# remote-displayV2.net
KiCad netlist of a schematic drawn in EAGLE
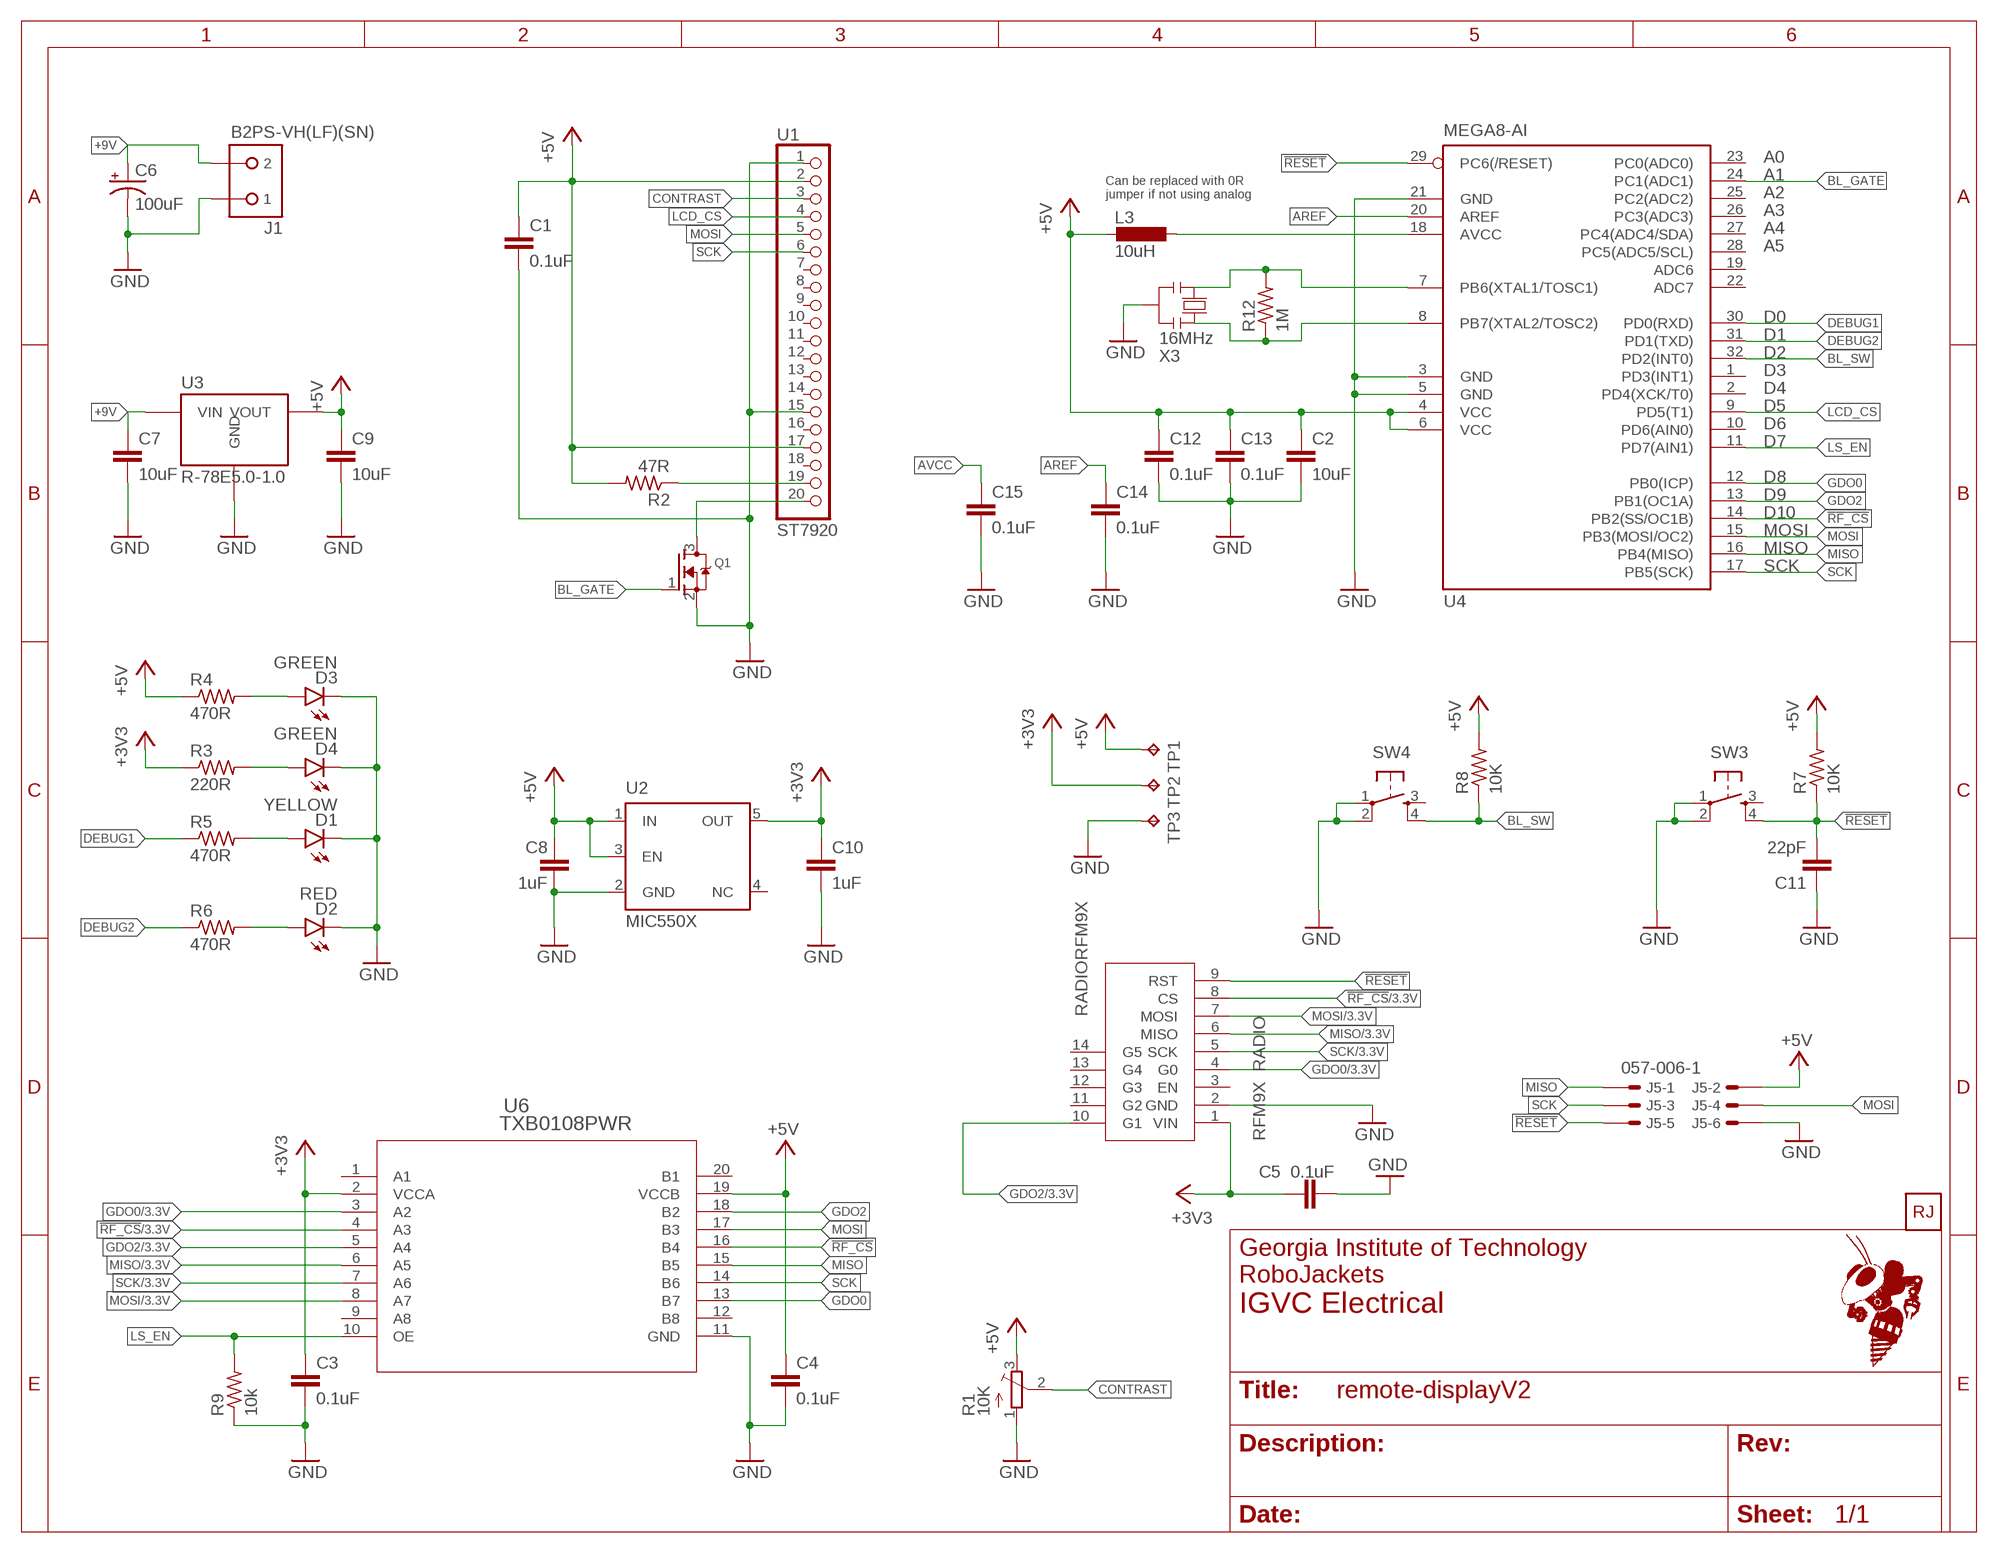
[diagram p0: schematic, sheet 1]

(export (version "E")
  (design (tool "Eeschema 10.0.6"))
  (components
    (comp (ref "C1")
      (value "0.1uF")
      (footprint "eagle-import:C0603")
      (libsource (lib "eagle-import") (part "resistor_348_C-EUC0603"))
    )
    (comp (ref "C2")
      (value "10uF")
      (footprint "eagle-import:C0805")
      (libsource (lib "eagle-import") (part "resistor_348_C-EUC0805"))
    )
    (comp (ref "C3")
      (value "0.1uF")
      (footprint "eagle-import:C0603")
      (libsource (lib "eagle-import") (part "C-EUC0603"))
    )
    (comp (ref "C4")
      (value "0.1uF")
      (footprint "eagle-import:C0603")
      (libsource (lib "eagle-import") (part "C-EUC0603"))
    )
    (comp (ref "C5")
      (value "0.1uF")
      (footprint "eagle-import:C0603")
      (libsource (lib "eagle-import") (part "resistor_348_C-EUC0603"))
    )
    (comp (ref "C6")
      (value "100uF")
      (footprint "eagle-import:E5-10,5")
      (libsource (lib "eagle-import") (part "CPOL-USE5-10.5"))
    )
    (comp (ref "C7")
      (value "10uF")
      (footprint "eagle-import:C0603")
      (libsource (lib "eagle-import") (part "C-EUC0603"))
    )
    (comp (ref "C8")
      (value "1uF")
      (footprint "eagle-import:C0603")
      (libsource (lib "eagle-import") (part "C-EUC0603"))
    )
    (comp (ref "C9")
      (value "10uF")
      (footprint "eagle-import:C0603")
      (libsource (lib "eagle-import") (part "C-EUC0603"))
    )
    (comp (ref "C10")
      (value "1uF")
      (footprint "eagle-import:C0603")
      (libsource (lib "eagle-import") (part "C-EUC0603"))
    )
    (comp (ref "C11")
      (value "22pF")
      (footprint "eagle-import:C0603")
      (libsource (lib "eagle-import") (part "resistor_348_C-EUC0603"))
    )
    (comp (ref "C12")
      (value "0.1uF")
      (footprint "eagle-import:C0603")
      (libsource (lib "eagle-import") (part "resistor_348_C-EUC0603"))
    )
    (comp (ref "C13")
      (value "0.1uF")
      (footprint "eagle-import:C0603")
      (libsource (lib "eagle-import") (part "resistor_348_C-EUC0603"))
    )
    (comp (ref "C14")
      (value "0.1uF")
      (footprint "eagle-import:C0603")
      (libsource (lib "eagle-import") (part "resistor_348_C-EUC0603"))
    )
    (comp (ref "C15")
      (value "0.1uF")
      (footprint "eagle-import:C0603")
      (libsource (lib "eagle-import") (part "resistor_348_C-EUC0603"))
    )
    (comp (ref "D1")
      (value "YELLOW")
      (footprint "eagle-import:LED3MM")
      (libsource (lib "eagle-import") (part "LED3MM"))
    )
    (comp (ref "D2")
      (value "RED")
      (footprint "eagle-import:LED3MM")
      (libsource (lib "eagle-import") (part "LED3MM"))
    )
    (comp (ref "D3")
      (value "GREEN")
      (footprint "eagle-import:LED3MM")
      (libsource (lib "eagle-import") (part "LED3MM"))
    )
    (comp (ref "D4")
      (value "GREEN")
      (footprint "eagle-import:LED3MM")
      (libsource (lib "eagle-import") (part "LED3MM"))
    )
    (comp (ref "J1")
      (value "B2PS-VH(LF)(SN)")
      (footprint "eagle-import:B2PS-CENTERED")
      (libsource (lib "eagle-import") (part "B2P?-VH(LF)(SN)S"))
    )
    (comp (ref "J5")
      (value "057-006-1")
      (footprint "eagle-import:057-006-1")
      (fields (field (name "DIGIKEY") "3M15451-ND"))
      (libsource (lib "eagle-import") (part "057-006-1"))
    )
    (comp (ref "L3")
      (value "10uH")
      (footprint "eagle-import:0805")
      (libsource (lib "eagle-import") (part "L-0805"))
    )
    (comp (ref "Q1")
      (value "MOSFET-NREFLOW")
      (footprint "eagle-import:SOT23")
      (libsource (lib "eagle-import") (part "MOSFET-NREFLOW"))
    )
    (comp (ref "R1")
      (value "10K")
      (footprint "eagle-import:TRIM-3386")
      (libsource (lib "eagle-import") (part "TRIMPOT3386"))
    )
    (comp (ref "R2")
      (value "47R")
      (footprint "eagle-import:R0805")
      (libsource (lib "eagle-import") (part "resistor_348_R-US_R0805"))
    )
    (comp (ref "R3")
      (value "220R")
      (footprint "eagle-import:R0603")
      (libsource (lib "eagle-import") (part "resistor_348_R-US_R0603"))
    )
    (comp (ref "R4")
      (value "470R")
      (footprint "eagle-import:R0603")
      (libsource (lib "eagle-import") (part "resistor_348_R-US_R0603"))
    )
    (comp (ref "R5")
      (value "470R")
      (footprint "eagle-import:R0603")
      (libsource (lib "eagle-import") (part "resistor_348_R-US_R0603"))
    )
    (comp (ref "R6")
      (value "470R")
      (footprint "eagle-import:R0603")
      (libsource (lib "eagle-import") (part "resistor_348_R-US_R0603"))
    )
    (comp (ref "R7")
      (value "10K")
      (footprint "eagle-import:R0603")
      (libsource (lib "eagle-import") (part "resistor_348_R-US_R0603"))
    )
    (comp (ref "R8")
      (value "10K")
      (footprint "eagle-import:R0603")
      (libsource (lib "eagle-import") (part "resistor_348_R-US_R0603"))
    )
    (comp (ref "R9")
      (value "10k")
      (footprint "eagle-import:R0603")
      (libsource (lib "eagle-import") (part "R-US_R0603"))
    )
    (comp (ref "R12")
      (value "1M")
      (footprint "eagle-import:R0603")
      (libsource (lib "eagle-import") (part "resistor_348_R-US_R0603"))
    )
    (comp (ref "SW3")
      (value "TL1105_A-H")
      (footprint "eagle-import:TL1105_A-H")
      (libsource (lib "eagle-import") (part "TL1105_A-H"))
    )
    (comp (ref "SW4")
      (value "TL1105_A-H")
      (footprint "eagle-import:TL1105_A-H")
      (libsource (lib "eagle-import") (part "TL1105_A-H"))
    )
    (comp (ref "TP1")
      (value "TPPAD1-17")
      (footprint "eagle-import:P1-17")
      (libsource (lib "eagle-import") (part "TPPAD1-17"))
    )
    (comp (ref "TP2")
      (value "TPPAD1-17")
      (footprint "eagle-import:P1-17")
      (libsource (lib "eagle-import") (part "TPPAD1-17"))
    )
    (comp (ref "TP3")
      (value "TPPAD1-17")
      (footprint "eagle-import:P1-17")
      (libsource (lib "eagle-import") (part "TPPAD1-17"))
    )
    (comp (ref "U$1")
      (value "RADIORFM9X")
      (footprint "eagle-import:RFM9X")
      (libsource (lib "eagle-import") (part "RADIORFM9X"))
    )
    (comp (ref "U$2")
      (value "ROBOBUZZ1.0X")
      (footprint "eagle-import:ROBOBUZZ_1.0X")
      (libsource (lib "eagle-import") (part "ROBOBUZZ1.0X"))
    )
    (comp (ref "U1")
      (value "ST7920")
      (footprint "eagle-import:ST7920-LCD")
      (libsource (lib "eagle-import") (part "ST7920"))
    )
    (comp (ref "U2")
      (value "MIC550X")
      (footprint "eagle-import:SOT23-DBV")
      (libsource (lib "eagle-import") (part "MIC550X"))
    )
    (comp (ref "U3")
      (value "R-78E5.0-1.0")
      (footprint "eagle-import:R-78E")
      (libsource (lib "eagle-import") (part "R-78E5.0-1.0"))
    )
    (comp (ref "U4")
      (value "MEGA8-AI")
      (footprint "eagle-import:TQFP32-08")
      (fields (field (name "MPN") "ATMEGA8-16AU"))
      (libsource (lib "eagle-import") (part "MEGA8-AI"))
    )
    (comp (ref "U6")
      (value "TXB0108PWR")
      (footprint "eagle-import:PW20")
      (libsource (lib "eagle-import") (part "TXB0108PWR"))
    )
    (comp (ref "X3")
      (value "16MHz")
      (footprint "eagle-import:RESONATOR")
      (fields (field (name "PART_NUMBER") "CSTCE16M0V53-R0"))
      (libsource (lib "eagle-import") (part "OSC_CSTCE16M0V53-R0"))
    )
  )
  (nets
    (net (code "1") (name "+3V3") (class "Default")
      (node (ref "C10") (pin "1") (pinfunction "1_1") (pintype "passive"))
      (node (ref "C3") (pin "1") (pinfunction "1_1") (pintype "passive"))
      (node (ref "C5") (pin "1") (pinfunction "1_1") (pintype "passive"))
      (node (ref "R3") (pin "1") (pinfunction "1_1") (pintype "passive"))
      (node (ref "TP2") (pin "TP") (pinfunction "TP_TP") (pintype "input"))
      (node (ref "U$1") (pin "1") (pinfunction "VIN_1") (pintype "bidirectional"))
      (node (ref "U2") (pin "5") (pinfunction "OUT_5") (pintype "passive"))
      (node (ref "U6") (pin "2") (pinfunction "VCCA_2") (pintype "power_in"))
    )
    (net (code "2") (name "+5V") (class "Default")
      (node (ref "C1") (pin "1") (pinfunction "1_1") (pintype "passive"))
      (node (ref "C12") (pin "1") (pinfunction "1_1") (pintype "passive"))
      (node (ref "C13") (pin "1") (pinfunction "1_1") (pintype "passive"))
      (node (ref "C2") (pin "1") (pinfunction "1_1") (pintype "passive"))
      (node (ref "C4") (pin "1") (pinfunction "1_1") (pintype "passive"))
      (node (ref "C8") (pin "1") (pinfunction "1_1") (pintype "passive"))
      (node (ref "C9") (pin "1") (pinfunction "1_1") (pintype "passive"))
      (node (ref "J5") (pin "2") (pinfunction "S_2") (pintype "passive"))
      (node (ref "L3") (pin "2") (pinfunction "2_2") (pintype "passive"))
      (node (ref "R1") (pin "3") (pinfunction "E_3") (pintype "passive"))
      (node (ref "R2") (pin "2") (pinfunction "2_2") (pintype "passive"))
      (node (ref "R4") (pin "1") (pinfunction "1_1") (pintype "passive"))
      (node (ref "R7") (pin "2") (pinfunction "2_2") (pintype "passive"))
      (node (ref "R8") (pin "2") (pinfunction "2_2") (pintype "passive"))
      (node (ref "TP1") (pin "TP") (pinfunction "TP_TP") (pintype "input"))
      (node (ref "U1") (pin "17") (pinfunction "17_17") (pintype "passive"))
      (node (ref "U1") (pin "2") (pinfunction "2_2") (pintype "passive"))
      (node (ref "U2") (pin "1") (pinfunction "IN_1") (pintype "input"))
      (node (ref "U2") (pin "3") (pinfunction "EN_3") (pintype "input"))
      (node (ref "U3") (pin "3") (pinfunction "VOUT_3") (pintype "bidirectional"))
      (node (ref "U4") (pin "4") (pinfunction "VCC_4") (pintype "power_in"))
      (node (ref "U4") (pin "6") (pinfunction "VCC_6") (pintype "power_in"))
      (node (ref "U6") (pin "19") (pinfunction "VCCB_19") (pintype "power_in"))
    )
    (net (code "3") (name "+9V") (class "Default")
      (node (ref "C6") (pin "+") (pinfunction "+_+") (pintype "passive"))
      (node (ref "C7") (pin "1") (pinfunction "1_1") (pintype "passive"))
      (node (ref "J1") (pin "2") (pinfunction "2_2") (pintype "bidirectional"))
      (node (ref "U3") (pin "1") (pinfunction "VIN_1") (pintype "bidirectional"))
    )
    (net (code "4") (name "/~{RESET}") (class "Default")
      (node (ref "C11") (pin "2") (pinfunction "2_2") (pintype "passive"))
      (node (ref "J5") (pin "5") (pinfunction "S_5") (pintype "passive"))
      (node (ref "R7") (pin "1") (pinfunction "1_1") (pintype "passive"))
      (node (ref "SW3") (pin "4") (pinfunction "4_4") (pintype "passive"))
      (node (ref "U$1") (pin "9") (pinfunction "RST_9") (pintype "bidirectional"))
      (node (ref "U4") (pin "29") (pinfunction "PC6(/RESET)_29") (pintype "bidirectional"))
    )
    (net (code "5") (name "/~{RF_CS}") (class "Default")
      (node (ref "U4") (pin "14") (pinfunction "PB2(SS/OC1B)_14") (pintype "bidirectional"))
      (node (ref "U6") (pin "16") (pinfunction "B4_16") (pintype "bidirectional"))
    )
    (net (code "6") (name "/~{RF_CS}{slash}3.3V") (class "Default")
      (node (ref "U$1") (pin "8") (pinfunction "CS_8") (pintype "bidirectional"))
      (node (ref "U6") (pin "4") (pinfunction "A3_4") (pintype "bidirectional"))
    )
    (net (code "7") (name "AREF") (class "Default")
      (node (ref "C14") (pin "1") (pinfunction "1_1") (pintype "passive"))
      (node (ref "U4") (pin "20") (pinfunction "AREF_20") (pintype "passive"))
    )
    (net (code "8") (name "AVCC") (class "Default")
      (node (ref "C15") (pin "1") (pinfunction "1_1") (pintype "passive"))
      (node (ref "L3") (pin "1") (pinfunction "1_1") (pintype "passive"))
      (node (ref "U4") (pin "18") (pinfunction "AVCC_18") (pintype "power_in"))
    )
    (net (code "9") (name "BL_GATE") (class "Default")
      (node (ref "Q1") (pin "1") (pinfunction "G_1") (pintype "bidirectional"))
      (node (ref "U4") (pin "24") (pinfunction "PC1(ADC1)_24") (pintype "bidirectional"))
    )
    (net (code "10") (name "BL_SW") (class "Default")
      (node (ref "R8") (pin "1") (pinfunction "1_1") (pintype "passive"))
      (node (ref "SW4") (pin "4") (pinfunction "4_4") (pintype "passive"))
      (node (ref "U4") (pin "32") (pinfunction "PD2(INT0)_32") (pintype "bidirectional"))
    )
    (net (code "11") (name "CONTRAST") (class "Default")
      (node (ref "R1") (pin "2") (pinfunction "S_2") (pintype "passive"))
      (node (ref "U1") (pin "3") (pinfunction "3_3") (pintype "passive"))
    )
    (net (code "12") (name "DEBUG1") (class "Default")
      (node (ref "R5") (pin "1") (pinfunction "1_1") (pintype "passive"))
      (node (ref "U4") (pin "30") (pinfunction "PD0(RXD)_30") (pintype "bidirectional"))
    )
    (net (code "13") (name "DEBUG2") (class "Default")
      (node (ref "R6") (pin "1") (pinfunction "1_1") (pintype "passive"))
      (node (ref "U4") (pin "31") (pinfunction "PD1(TXD)_31") (pintype "bidirectional"))
    )
    (net (code "14") (name "GDO0") (class "Default")
      (node (ref "U4") (pin "12") (pinfunction "PB0(ICP)_12") (pintype "bidirectional"))
      (node (ref "U6") (pin "13") (pinfunction "B7_13") (pintype "bidirectional"))
    )
    (net (code "15") (name "GDO0{slash}3.3V") (class "Default")
      (node (ref "U$1") (pin "4") (pinfunction "G0_4") (pintype "bidirectional"))
      (node (ref "U6") (pin "3") (pinfunction "A2_3") (pintype "bidirectional"))
    )
    (net (code "16") (name "GDO2") (class "Default")
      (node (ref "U4") (pin "13") (pinfunction "PB1(OC1A)_13") (pintype "bidirectional"))
      (node (ref "U6") (pin "18") (pinfunction "B2_18") (pintype "bidirectional"))
    )
    (net (code "17") (name "GDO2{slash}3.3V") (class "Default")
      (node (ref "U$1") (pin "10") (pinfunction "G1_10") (pintype "bidirectional"))
      (node (ref "U6") (pin "5") (pinfunction "A4_5") (pintype "bidirectional"))
    )
    (net (code "18") (name "GND") (class "Default")
      (node (ref "C1") (pin "2") (pinfunction "2_2") (pintype "passive"))
      (node (ref "C10") (pin "2") (pinfunction "2_2") (pintype "passive"))
      (node (ref "C11") (pin "1") (pinfunction "1_1") (pintype "passive"))
      (node (ref "C12") (pin "2") (pinfunction "2_2") (pintype "passive"))
      (node (ref "C13") (pin "2") (pinfunction "2_2") (pintype "passive"))
      (node (ref "C14") (pin "2") (pinfunction "2_2") (pintype "passive"))
      (node (ref "C15") (pin "2") (pinfunction "2_2") (pintype "passive"))
      (node (ref "C2") (pin "2") (pinfunction "2_2") (pintype "passive"))
      (node (ref "C3") (pin "2") (pinfunction "2_2") (pintype "passive"))
      (node (ref "C4") (pin "2") (pinfunction "2_2") (pintype "passive"))
      (node (ref "C5") (pin "2") (pinfunction "2_2") (pintype "passive"))
      (node (ref "C6") (pin "-") (pinfunction "-_-") (pintype "passive"))
      (node (ref "C7") (pin "2") (pinfunction "2_2") (pintype "passive"))
      (node (ref "C8") (pin "2") (pinfunction "2_2") (pintype "passive"))
      (node (ref "C9") (pin "2") (pinfunction "2_2") (pintype "passive"))
      (node (ref "D1") (pin "K") (pinfunction "C_K") (pintype "passive"))
      (node (ref "D2") (pin "K") (pinfunction "C_K") (pintype "passive"))
      (node (ref "D3") (pin "K") (pinfunction "C_K") (pintype "passive"))
      (node (ref "D4") (pin "K") (pinfunction "C_K") (pintype "passive"))
      (node (ref "J1") (pin "1") (pinfunction "1_1") (pintype "bidirectional"))
      (node (ref "J5") (pin "6") (pinfunction "S_6") (pintype "passive"))
      (node (ref "Q1") (pin "2") (pinfunction "S_2") (pintype "bidirectional"))
      (node (ref "R1") (pin "1") (pinfunction "A_1") (pintype "passive"))
      (node (ref "R9") (pin "1") (pinfunction "1_1") (pintype "passive"))
      (node (ref "SW3") (pin "1") (pinfunction "1_1") (pintype "passive"))
      (node (ref "SW3") (pin "2") (pinfunction "2_2") (pintype "passive"))
      (node (ref "SW4") (pin "1") (pinfunction "1_1") (pintype "passive"))
      (node (ref "SW4") (pin "2") (pinfunction "2_2") (pintype "passive"))
      (node (ref "TP3") (pin "TP") (pinfunction "TP_TP") (pintype "input"))
      (node (ref "U$1") (pin "2") (pinfunction "GND_2") (pintype "bidirectional"))
      (node (ref "U1") (pin "1") (pinfunction "1_1") (pintype "passive"))
      (node (ref "U1") (pin "15") (pinfunction "15_15") (pintype "passive"))
      (node (ref "U2") (pin "2") (pinfunction "GND_2") (pintype "output"))
      (node (ref "U3") (pin "2") (pinfunction "GND_2") (pintype "bidirectional"))
      (node (ref "U4") (pin "21") (pinfunction "GND_21") (pintype "power_in"))
      (node (ref "U4") (pin "3") (pinfunction "GND_3") (pintype "power_in"))
      (node (ref "U4") (pin "5") (pinfunction "GND_5") (pintype "power_in"))
      (node (ref "U6") (pin "11") (pinfunction "GND_11") (pintype "power_in"))
      (node (ref "X3") (pin "2") (pinfunction "2_2") (pintype "passive"))
    )
    (net (code "19") (name "LCD_CS") (class "Default")
      (node (ref "U1") (pin "4") (pinfunction "4_4") (pintype "passive"))
      (node (ref "U4") (pin "9") (pinfunction "PD5(T1)_9") (pintype "bidirectional"))
    )
    (net (code "20") (name "LS_EN") (class "Default")
      (node (ref "R9") (pin "2") (pinfunction "2_2") (pintype "passive"))
      (node (ref "U4") (pin "11") (pinfunction "PD7(AIN1)_11") (pintype "bidirectional"))
      (node (ref "U6") (pin "10") (pinfunction "OE_10") (pintype "output"))
    )
    (net (code "21") (name "MISO") (class "Default")
      (node (ref "J5") (pin "1") (pinfunction "S_1") (pintype "passive"))
      (node (ref "U4") (pin "16") (pinfunction "PB4(MISO)_16") (pintype "bidirectional"))
      (node (ref "U6") (pin "15") (pinfunction "B5_15") (pintype "bidirectional"))
    )
    (net (code "22") (name "MISO{slash}3.3V") (class "Default")
      (node (ref "U$1") (pin "6") (pinfunction "MISO_6") (pintype "bidirectional"))
      (node (ref "U6") (pin "6") (pinfunction "A5_6") (pintype "bidirectional"))
    )
    (net (code "23") (name "MOSI") (class "Default")
      (node (ref "J5") (pin "4") (pinfunction "S_4") (pintype "passive"))
      (node (ref "U1") (pin "5") (pinfunction "5_5") (pintype "passive"))
      (node (ref "U4") (pin "15") (pinfunction "PB3(MOSI/OC2)_15") (pintype "bidirectional"))
      (node (ref "U6") (pin "17") (pinfunction "B3_17") (pintype "bidirectional"))
    )
    (net (code "24") (name "MOSI{slash}3.3V") (class "Default")
      (node (ref "U$1") (pin "7") (pinfunction "MOSI_7") (pintype "bidirectional"))
      (node (ref "U6") (pin "8") (pinfunction "A7_8") (pintype "bidirectional"))
    )
    (net (code "25") (name "Net-(D1-PadA)") (class "Default")
      (node (ref "D1") (pin "A") (pinfunction "A_A") (pintype "passive"))
      (node (ref "R5") (pin "2") (pinfunction "2_2") (pintype "passive"))
    )
    (net (code "26") (name "Net-(D2-PadA)") (class "Default")
      (node (ref "D2") (pin "A") (pinfunction "A_A") (pintype "passive"))
      (node (ref "R6") (pin "2") (pinfunction "2_2") (pintype "passive"))
    )
    (net (code "27") (name "Net-(D3-PadA)") (class "Default")
      (node (ref "D3") (pin "A") (pinfunction "A_A") (pintype "passive"))
      (node (ref "R4") (pin "2") (pinfunction "2_2") (pintype "passive"))
    )
    (net (code "28") (name "Net-(D4-PadA)") (class "Default")
      (node (ref "D4") (pin "A") (pinfunction "A_A") (pintype "passive"))
      (node (ref "R3") (pin "2") (pinfunction "2_2") (pintype "passive"))
    )
    (net (code "29") (name "Net-(Q1-D)") (class "Default")
      (node (ref "Q1") (pin "3") (pinfunction "D_3") (pintype "bidirectional"))
      (node (ref "U1") (pin "20") (pinfunction "20_20") (pintype "passive"))
    )
    (net (code "30") (name "Net-(R2-Pad1)") (class "Default")
      (node (ref "R2") (pin "1") (pinfunction "1_1") (pintype "passive"))
      (node (ref "U1") (pin "19") (pinfunction "19_19") (pintype "passive"))
    )
    (net (code "31") (name "Net-(U4-PB6(XTAL1{slash}TOSC1))") (class "Default")
      (node (ref "R12") (pin "2") (pinfunction "2_2") (pintype "passive"))
      (node (ref "U4") (pin "7") (pinfunction "PB6(XTAL1/TOSC1)_7") (pintype "bidirectional"))
      (node (ref "X3") (pin "1") (pinfunction "1_1") (pintype "passive"))
    )
    (net (code "32") (name "Net-(U4-PB7(XTAL2{slash}TOSC2))") (class "Default")
      (node (ref "R12") (pin "1") (pinfunction "1_1") (pintype "passive"))
      (node (ref "U4") (pin "8") (pinfunction "PB7(XTAL2/TOSC2)_8") (pintype "bidirectional"))
      (node (ref "X3") (pin "3") (pinfunction "3_3") (pintype "passive"))
    )
    (net (code "33") (name "SCK") (class "Default")
      (node (ref "J5") (pin "3") (pinfunction "S_3") (pintype "passive"))
      (node (ref "U1") (pin "6") (pinfunction "6_6") (pintype "passive"))
      (node (ref "U4") (pin "17") (pinfunction "PB5(SCK)_17") (pintype "bidirectional"))
      (node (ref "U6") (pin "14") (pinfunction "B6_14") (pintype "bidirectional"))
    )
    (net (code "34") (name "SCK{slash}3.3V") (class "Default")
      (node (ref "U$1") (pin "5") (pinfunction "SCK_5") (pintype "bidirectional"))
      (node (ref "U6") (pin "7") (pinfunction "A6_7") (pintype "bidirectional"))
    )
    (net (code "35") (name "unconnected-(SW3-Pad3)") (class "Default")
      (node (ref "SW3") (pin "3") (pinfunction "3_3") (pintype "passive"))
    )
    (net (code "36") (name "unconnected-(SW4-Pad3)") (class "Default")
      (node (ref "SW4") (pin "3") (pinfunction "3_3") (pintype "passive"))
    )
    (net (code "37") (name "unconnected-(U$1-EN-Pad3)") (class "Default")
      (node (ref "U$1") (pin "3") (pinfunction "EN_3") (pintype "bidirectional"))
    )
    (net (code "38") (name "unconnected-(U$1-G2-Pad11)") (class "Default")
      (node (ref "U$1") (pin "11") (pinfunction "G2_11") (pintype "bidirectional"))
    )
    (net (code "39") (name "unconnected-(U$1-G3-Pad12)") (class "Default")
      (node (ref "U$1") (pin "12") (pinfunction "G3_12") (pintype "bidirectional"))
    )
    (net (code "40") (name "unconnected-(U$1-G4-Pad13)") (class "Default")
      (node (ref "U$1") (pin "13") (pinfunction "G4_13") (pintype "bidirectional"))
    )
    (net (code "41") (name "unconnected-(U$1-G5-Pad14)") (class "Default")
      (node (ref "U$1") (pin "14") (pinfunction "G5_14") (pintype "bidirectional"))
    )
    (net (code "42") (name "unconnected-(U1-Pad7)") (class "Default")
      (node (ref "U1") (pin "7") (pinfunction "7_7") (pintype "passive"))
    )
    (net (code "43") (name "unconnected-(U1-Pad8)") (class "Default")
      (node (ref "U1") (pin "8") (pinfunction "8_8") (pintype "passive"))
    )
    (net (code "44") (name "unconnected-(U1-Pad9)") (class "Default")
      (node (ref "U1") (pin "9") (pinfunction "9_9") (pintype "passive"))
    )
    (net (code "45") (name "unconnected-(U1-Pad10)") (class "Default")
      (node (ref "U1") (pin "10") (pinfunction "10_10") (pintype "passive"))
    )
    (net (code "46") (name "unconnected-(U1-Pad11)") (class "Default")
      (node (ref "U1") (pin "11") (pinfunction "11_11") (pintype "passive"))
    )
    (net (code "47") (name "unconnected-(U1-Pad12)") (class "Default")
      (node (ref "U1") (pin "12") (pinfunction "12_12") (pintype "passive"))
    )
    (net (code "48") (name "unconnected-(U1-Pad13)") (class "Default")
      (node (ref "U1") (pin "13") (pinfunction "13_13") (pintype "passive"))
    )
    (net (code "49") (name "unconnected-(U1-Pad14)") (class "Default")
      (node (ref "U1") (pin "14") (pinfunction "14_14") (pintype "passive"))
    )
    (net (code "50") (name "unconnected-(U1-Pad16)") (class "Default")
      (node (ref "U1") (pin "16") (pinfunction "16_16") (pintype "passive"))
    )
    (net (code "51") (name "unconnected-(U1-Pad18)") (class "Default")
      (node (ref "U1") (pin "18") (pinfunction "18_18") (pintype "passive"))
    )
    (net (code "52") (name "unconnected-(U2-NC-Pad4)") (class "Default")
      (node (ref "U2") (pin "4") (pinfunction "NC_4") (pintype "tri_state"))
    )
    (net (code "53") (name "unconnected-(U4-ADC6-Pad19)") (class "Default")
      (node (ref "U4") (pin "19") (pinfunction "ADC6_19") (pintype "bidirectional"))
    )
    (net (code "54") (name "unconnected-(U4-ADC7-Pad22)") (class "Default")
      (node (ref "U4") (pin "22") (pinfunction "ADC7_22") (pintype "bidirectional"))
    )
    (net (code "55") (name "unconnected-(U4-PC0(ADC0)-Pad23)") (class "Default")
      (node (ref "U4") (pin "23") (pinfunction "PC0(ADC0)_23") (pintype "bidirectional"))
    )
    (net (code "56") (name "unconnected-(U4-PC2(ADC2)-Pad25)") (class "Default")
      (node (ref "U4") (pin "25") (pinfunction "PC2(ADC2)_25") (pintype "bidirectional"))
    )
    (net (code "57") (name "unconnected-(U4-PC3(ADC3)-Pad26)") (class "Default")
      (node (ref "U4") (pin "26") (pinfunction "PC3(ADC3)_26") (pintype "bidirectional"))
    )
    (net (code "58") (name "unconnected-(U4-PC4(ADC4{slash}SDA)-Pad27)") (class "Default")
      (node (ref "U4") (pin "27") (pinfunction "PC4(ADC4/SDA)_27") (pintype "bidirectional"))
    )
    (net (code "59") (name "unconnected-(U4-PC5(ADC5{slash}SCL)-Pad28)") (class "Default")
      (node (ref "U4") (pin "28") (pinfunction "PC5(ADC5/SCL)_28") (pintype "bidirectional"))
    )
    (net (code "60") (name "unconnected-(U4-PD3(INT1)-Pad1)") (class "Default")
      (node (ref "U4") (pin "1") (pinfunction "PD3(INT1)_1") (pintype "bidirectional"))
    )
    (net (code "61") (name "unconnected-(U4-PD4(XCK{slash}T0)-Pad2)") (class "Default")
      (node (ref "U4") (pin "2") (pinfunction "PD4(XCK/T0)_2") (pintype "bidirectional"))
    )
    (net (code "62") (name "unconnected-(U4-PD6(AIN0)-Pad10)") (class "Default")
      (node (ref "U4") (pin "10") (pinfunction "PD6(AIN0)_10") (pintype "bidirectional"))
    )
    (net (code "63") (name "unconnected-(U6-A1-Pad1)") (class "Default")
      (node (ref "U6") (pin "1") (pinfunction "A1_1") (pintype "bidirectional"))
    )
    (net (code "64") (name "unconnected-(U6-A8-Pad9)") (class "Default")
      (node (ref "U6") (pin "9") (pinfunction "A8_9") (pintype "bidirectional"))
    )
    (net (code "65") (name "unconnected-(U6-B1-Pad20)") (class "Default")
      (node (ref "U6") (pin "20") (pinfunction "B1_20") (pintype "bidirectional"))
    )
    (net (code "66") (name "unconnected-(U6-B8-Pad12)") (class "Default")
      (node (ref "U6") (pin "12") (pinfunction "B8_12") (pintype "bidirectional"))
    )
  )
)
